# Schematic_Altium.net
KiCad netlist of a schematic drawn in Altium Designer
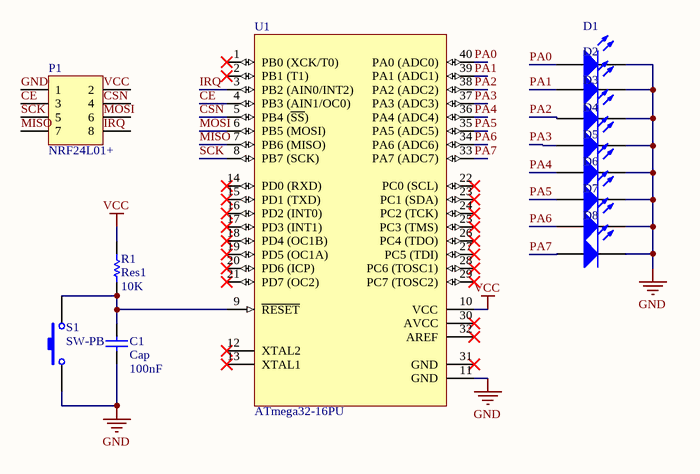
[diagram p0: Schematic_Altium.SchDoc]

(export (version "E")
  (design (tool "Eeschema 10.0.6"))
  (components
    (comp (ref "C1")
      (value "Cap")
      (footprint "RAD-0.3")
      (description "Capacitor")
      (fields (field (name "ALTIUM_VALUE") "100nF") (field (name "PUBLISHER") "Altium Limited"))
      (libsource (lib "Miscellaneous Devices") (part "Cap"))
    )
    (comp (ref "D1")
      (value "LED0")
      (footprint "LED-0")
      (description "Typical INFRARED GaAs LED")
      (fields (field (name "PUBLISHER") "Altium Limited"))
      (libsource (lib "Miscellaneous Devices") (part "LED0"))
    )
    (comp (ref "D2")
      (value "LED0")
      (footprint "LED-0")
      (description "Typical INFRARED GaAs LED")
      (fields (field (name "PUBLISHER") "Altium Limited"))
      (libsource (lib "Miscellaneous Devices") (part "LED0"))
    )
    (comp (ref "D3")
      (value "LED0")
      (footprint "LED-0")
      (description "Typical INFRARED GaAs LED")
      (fields (field (name "PUBLISHER") "Altium Limited"))
      (libsource (lib "Miscellaneous Devices") (part "LED0"))
    )
    (comp (ref "D4")
      (value "LED0")
      (footprint "LED-0")
      (description "Typical INFRARED GaAs LED")
      (fields (field (name "PUBLISHER") "Altium Limited"))
      (libsource (lib "Miscellaneous Devices") (part "LED0"))
    )
    (comp (ref "D5")
      (value "LED0")
      (footprint "LED-0")
      (description "Typical INFRARED GaAs LED")
      (fields (field (name "PUBLISHER") "Altium Limited"))
      (libsource (lib "Miscellaneous Devices") (part "LED0"))
    )
    (comp (ref "D6")
      (value "LED0")
      (footprint "LED-0")
      (description "Typical INFRARED GaAs LED")
      (fields (field (name "PUBLISHER") "Altium Limited"))
      (libsource (lib "Miscellaneous Devices") (part "LED0"))
    )
    (comp (ref "D7")
      (value "LED0")
      (footprint "LED-0")
      (description "Typical INFRARED GaAs LED")
      (fields (field (name "PUBLISHER") "Altium Limited"))
      (libsource (lib "Miscellaneous Devices") (part "LED0"))
    )
    (comp (ref "D8")
      (value "LED0")
      (footprint "LED-0")
      (description "Typical INFRARED GaAs LED")
      (fields (field (name "PUBLISHER") "Altium Limited"))
      (libsource (lib "Miscellaneous Devices") (part "LED0"))
    )
    (comp (ref "P1")
      (value "NRF24L01+")
      (footprint "HDR2X4")
      (description "Header, 4-Pin, Dual row")
      (fields (field (name "PUBLISHER") "Altium Limited"))
      (libsource (lib "Miscellaneous Connectors") (part "Header 4X2"))
    )
    (comp (ref "R1")
      (value "Res1")
      (footprint "AXIAL-0.3")
      (description "Resistor")
      (fields (field (name "ALTIUM_VALUE") "10K") (field (name "PUBLISHER") "Altium Limited"))
      (libsource (lib "Miscellaneous Devices") (part "Res1"))
    )
    (comp (ref "S1")
      (value "SW-PB")
      (footprint "SPST-2")
      (description "Switch")
      (fields (field (name "PUBLISHER") "Altium Limited"))
      (libsource (lib "Miscellaneous Devices") (part "SW-PB"))
    )
    (comp (ref "U1")
      (value "ATmega32-16PU")
      (footprint "40P6")
      (libsource (lib "Atmel Microcontroller megaAVR") (part "ATmega32-16PU"))
    )
  )
  (nets
    (net (code "1") (name "/CE") (class "Default")
      (node (ref "P1") (pin "3") (pinfunction "3_3") (pintype "passive"))
      (node (ref "U1") (pin "4") (pinfunction "PB3_(AIN1/OC0)_4") (pintype "bidirectional"))
    )
    (net (code "2") (name "/CSN") (class "Default")
      (node (ref "U1") (pin "5") (pinfunction "PB4_(~{SS})_5") (pintype "bidirectional"))
    )
    (net (code "3") (name "/IRQ") (class "Default")
      (node (ref "U1") (pin "3") (pinfunction "PB2_(AIN0/INT2)_3") (pintype "bidirectional"))
    )
    (net (code "4") (name "/MISO") (class "Default")
      (node (ref "P1") (pin "7") (pinfunction "7_7") (pintype "passive"))
      (node (ref "U1") (pin "7") (pinfunction "PB6_(MISO)_7") (pintype "bidirectional"))
    )
    (net (code "5") (name "/MOSI") (class "Default")
      (node (ref "U1") (pin "6") (pinfunction "PB5_(MOSI)_6") (pintype "bidirectional"))
    )
    (net (code "6") (name "/PA0") (class "Default")
      (node (ref "D1") (pin "1") (pinfunction "A_1") (pintype "passive"))
      (node (ref "U1") (pin "40") (pinfunction "PA0_(ADC0)_40") (pintype "bidirectional"))
    )
    (net (code "7") (name "/PA1") (class "Default")
      (node (ref "D2") (pin "1") (pinfunction "A_1") (pintype "passive"))
      (node (ref "U1") (pin "39") (pinfunction "PA1_(ADC1)_39") (pintype "bidirectional"))
    )
    (net (code "8") (name "/PA2") (class "Default")
      (node (ref "D3") (pin "1") (pinfunction "A_1") (pintype "passive"))
      (node (ref "U1") (pin "38") (pinfunction "PA2_(ADC2)_38") (pintype "bidirectional"))
    )
    (net (code "9") (name "/PA3") (class "Default")
      (node (ref "U1") (pin "37") (pinfunction "PA3_(ADC3)_37") (pintype "bidirectional"))
    )
    (net (code "10") (name "/PA4") (class "Default")
      (node (ref "D5") (pin "1") (pinfunction "A_1") (pintype "passive"))
      (node (ref "U1") (pin "36") (pinfunction "PA4_(ADC4)_36") (pintype "bidirectional"))
    )
    (net (code "11") (name "/PA5") (class "Default")
      (node (ref "D6") (pin "1") (pinfunction "A_1") (pintype "passive"))
      (node (ref "U1") (pin "35") (pinfunction "PA5_(ADC5)_35") (pintype "bidirectional"))
    )
    (net (code "12") (name "/PA6") (class "Default")
      (node (ref "D7") (pin "1") (pinfunction "A_1") (pintype "passive"))
      (node (ref "U1") (pin "34") (pinfunction "PA6_(ADC6)_34") (pintype "bidirectional"))
    )
    (net (code "13") (name "/PA7") (class "Default")
      (node (ref "D8") (pin "1") (pinfunction "A_1") (pintype "passive"))
      (node (ref "U1") (pin "33") (pinfunction "PA7_(ADC7)_33") (pintype "bidirectional"))
    )
    (net (code "14") (name "/SCK") (class "Default")
      (node (ref "P1") (pin "5") (pinfunction "5_5") (pintype "passive"))
      (node (ref "U1") (pin "8") (pinfunction "PB7_(SCK)_8") (pintype "bidirectional"))
    )
    (net (code "15") (name "GND") (class "Default")
      (node (ref "C1") (pin "1") (pinfunction "1_1") (pintype "passive"))
      (node (ref "D1") (pin "2") (pinfunction "K_2") (pintype "passive"))
      (node (ref "D2") (pin "2") (pinfunction "K_2") (pintype "passive"))
      (node (ref "D3") (pin "2") (pinfunction "K_2") (pintype "passive"))
      (node (ref "D4") (pin "2") (pinfunction "K_2") (pintype "passive"))
      (node (ref "D5") (pin "2") (pinfunction "K_2") (pintype "passive"))
      (node (ref "D6") (pin "2") (pinfunction "K_2") (pintype "passive"))
      (node (ref "D7") (pin "2") (pinfunction "K_2") (pintype "passive"))
      (node (ref "D8") (pin "2") (pinfunction "K_2") (pintype "passive"))
      (node (ref "P1") (pin "1") (pinfunction "1_1") (pintype "passive"))
      (node (ref "S1") (pin "1") (pinfunction "1_1") (pintype "passive"))
      (node (ref "U1") (pin "11") (pinfunction "GND_11") (pintype "power_in"))
    )
    (net (code "16") (name "Net-(U1-~{RESET})") (class "Default")
      (node (ref "C1") (pin "2") (pinfunction "2_2") (pintype "passive"))
      (node (ref "R1") (pin "1") (pinfunction "1_1") (pintype "passive"))
      (node (ref "S1") (pin "2") (pinfunction "2_2") (pintype "passive"))
      (node (ref "U1") (pin "9") (pinfunction "~{RESET}_9") (pintype "input"))
    )
    (net (code "17") (name "VCC") (class "Default")
      (node (ref "R1") (pin "2") (pinfunction "2_2") (pintype "passive"))
      (node (ref "U1") (pin "10") (pinfunction "VCC_10") (pintype "power_in"))
    )
    (net (code "18") (name "unconnected-(D4-A-Pad1)") (class "Default")
      (node (ref "D4") (pin "1") (pinfunction "A_1") (pintype "passive"))
    )
    (net (code "19") (name "unconnected-(P1-Pad2)") (class "Default")
      (node (ref "P1") (pin "2") (pinfunction "2_2") (pintype "passive"))
    )
    (net (code "20") (name "unconnected-(P1-Pad4)") (class "Default")
      (node (ref "P1") (pin "4") (pinfunction "4_4") (pintype "passive"))
    )
    (net (code "21") (name "unconnected-(P1-Pad6)") (class "Default")
      (node (ref "P1") (pin "6") (pinfunction "6_6") (pintype "passive"))
    )
    (net (code "22") (name "unconnected-(P1-Pad8)") (class "Default")
      (node (ref "P1") (pin "8") (pinfunction "8_8") (pintype "passive"))
    )
    (net (code "23") (name "unconnected-(U1-AREF-Pad32)") (class "Default")
      (node (ref "U1") (pin "32") (pinfunction "AREF_32") (pintype "passive+no_connect"))
    )
    (net (code "24") (name "unconnected-(U1-AVCC-Pad30)") (class "Default")
      (node (ref "U1") (pin "30") (pinfunction "AVCC_30") (pintype "power_in+no_connect"))
    )
    (net (code "25") (name "unconnected-(U1-GND-Pad31)") (class "Default")
      (node (ref "U1") (pin "31") (pinfunction "GND_31") (pintype "power_in+no_connect"))
    )
    (net (code "26") (name "unconnected-(U1-PB0_(XCK{slash}T0)-Pad1)") (class "Default")
      (node (ref "U1") (pin "1") (pinfunction "PB0_(XCK/T0)_1") (pintype "bidirectional+no_connect"))
    )
    (net (code "27") (name "unconnected-(U1-PB1_(T1)-Pad2)") (class "Default")
      (node (ref "U1") (pin "2") (pinfunction "PB1_(T1)_2") (pintype "bidirectional+no_connect"))
    )
    (net (code "28") (name "unconnected-(U1-PC0_(SCL)-Pad22)") (class "Default")
      (node (ref "U1") (pin "22") (pinfunction "PC0_(SCL)_22") (pintype "bidirectional+no_connect"))
    )
    (net (code "29") (name "unconnected-(U1-PC1_(SDA)-Pad23)") (class "Default")
      (node (ref "U1") (pin "23") (pinfunction "PC1_(SDA)_23") (pintype "bidirectional+no_connect"))
    )
    (net (code "30") (name "unconnected-(U1-PC2_(TCK)-Pad24)") (class "Default")
      (node (ref "U1") (pin "24") (pinfunction "PC2_(TCK)_24") (pintype "bidirectional+no_connect"))
    )
    (net (code "31") (name "unconnected-(U1-PC3_(TMS)-Pad25)") (class "Default")
      (node (ref "U1") (pin "25") (pinfunction "PC3_(TMS)_25") (pintype "bidirectional+no_connect"))
    )
    (net (code "32") (name "unconnected-(U1-PC4_(TDO)-Pad26)") (class "Default")
      (node (ref "U1") (pin "26") (pinfunction "PC4_(TDO)_26") (pintype "bidirectional+no_connect"))
    )
    (net (code "33") (name "unconnected-(U1-PC5_(TDI)-Pad27)") (class "Default")
      (node (ref "U1") (pin "27") (pinfunction "PC5_(TDI)_27") (pintype "bidirectional+no_connect"))
    )
    (net (code "34") (name "unconnected-(U1-PC6_(TOSC1)-Pad28)") (class "Default")
      (node (ref "U1") (pin "28") (pinfunction "PC6_(TOSC1)_28") (pintype "bidirectional+no_connect"))
    )
    (net (code "35") (name "unconnected-(U1-PC7_(TOSC2)-Pad29)") (class "Default")
      (node (ref "U1") (pin "29") (pinfunction "PC7_(TOSC2)_29") (pintype "bidirectional+no_connect"))
    )
    (net (code "36") (name "unconnected-(U1-PD0_(RXD)-Pad14)") (class "Default")
      (node (ref "U1") (pin "14") (pinfunction "PD0_(RXD)_14") (pintype "bidirectional+no_connect"))
    )
    (net (code "37") (name "unconnected-(U1-PD1_(TXD)-Pad15)") (class "Default")
      (node (ref "U1") (pin "15") (pinfunction "PD1_(TXD)_15") (pintype "bidirectional+no_connect"))
    )
    (net (code "38") (name "unconnected-(U1-PD2_(INT0)-Pad16)") (class "Default")
      (node (ref "U1") (pin "16") (pinfunction "PD2_(INT0)_16") (pintype "bidirectional+no_connect"))
    )
    (net (code "39") (name "unconnected-(U1-PD3_(INT1)-Pad17)") (class "Default")
      (node (ref "U1") (pin "17") (pinfunction "PD3_(INT1)_17") (pintype "bidirectional+no_connect"))
    )
    (net (code "40") (name "unconnected-(U1-PD4_(OC1B)-Pad18)") (class "Default")
      (node (ref "U1") (pin "18") (pinfunction "PD4_(OC1B)_18") (pintype "bidirectional+no_connect"))
    )
    (net (code "41") (name "unconnected-(U1-PD5_(OC1A)-Pad19)") (class "Default")
      (node (ref "U1") (pin "19") (pinfunction "PD5_(OC1A)_19") (pintype "bidirectional+no_connect"))
    )
    (net (code "42") (name "unconnected-(U1-PD6_(ICP)-Pad20)") (class "Default")
      (node (ref "U1") (pin "20") (pinfunction "PD6_(ICP)_20") (pintype "bidirectional+no_connect"))
    )
    (net (code "43") (name "unconnected-(U1-PD7_(OC2)-Pad21)") (class "Default")
      (node (ref "U1") (pin "21") (pinfunction "PD7_(OC2)_21") (pintype "bidirectional+no_connect"))
    )
    (net (code "44") (name "unconnected-(U1-XTAL1-Pad13)") (class "Default")
      (node (ref "U1") (pin "13") (pinfunction "XTAL1_13") (pintype "passive+no_connect"))
    )
    (net (code "45") (name "unconnected-(U1-XTAL2-Pad12)") (class "Default")
      (node (ref "U1") (pin "12") (pinfunction "XTAL2_12") (pintype "passive+no_connect"))
    )
  )
)
